# DE-300617.net
KiCad netlist of a schematic drawn in Altium Designer
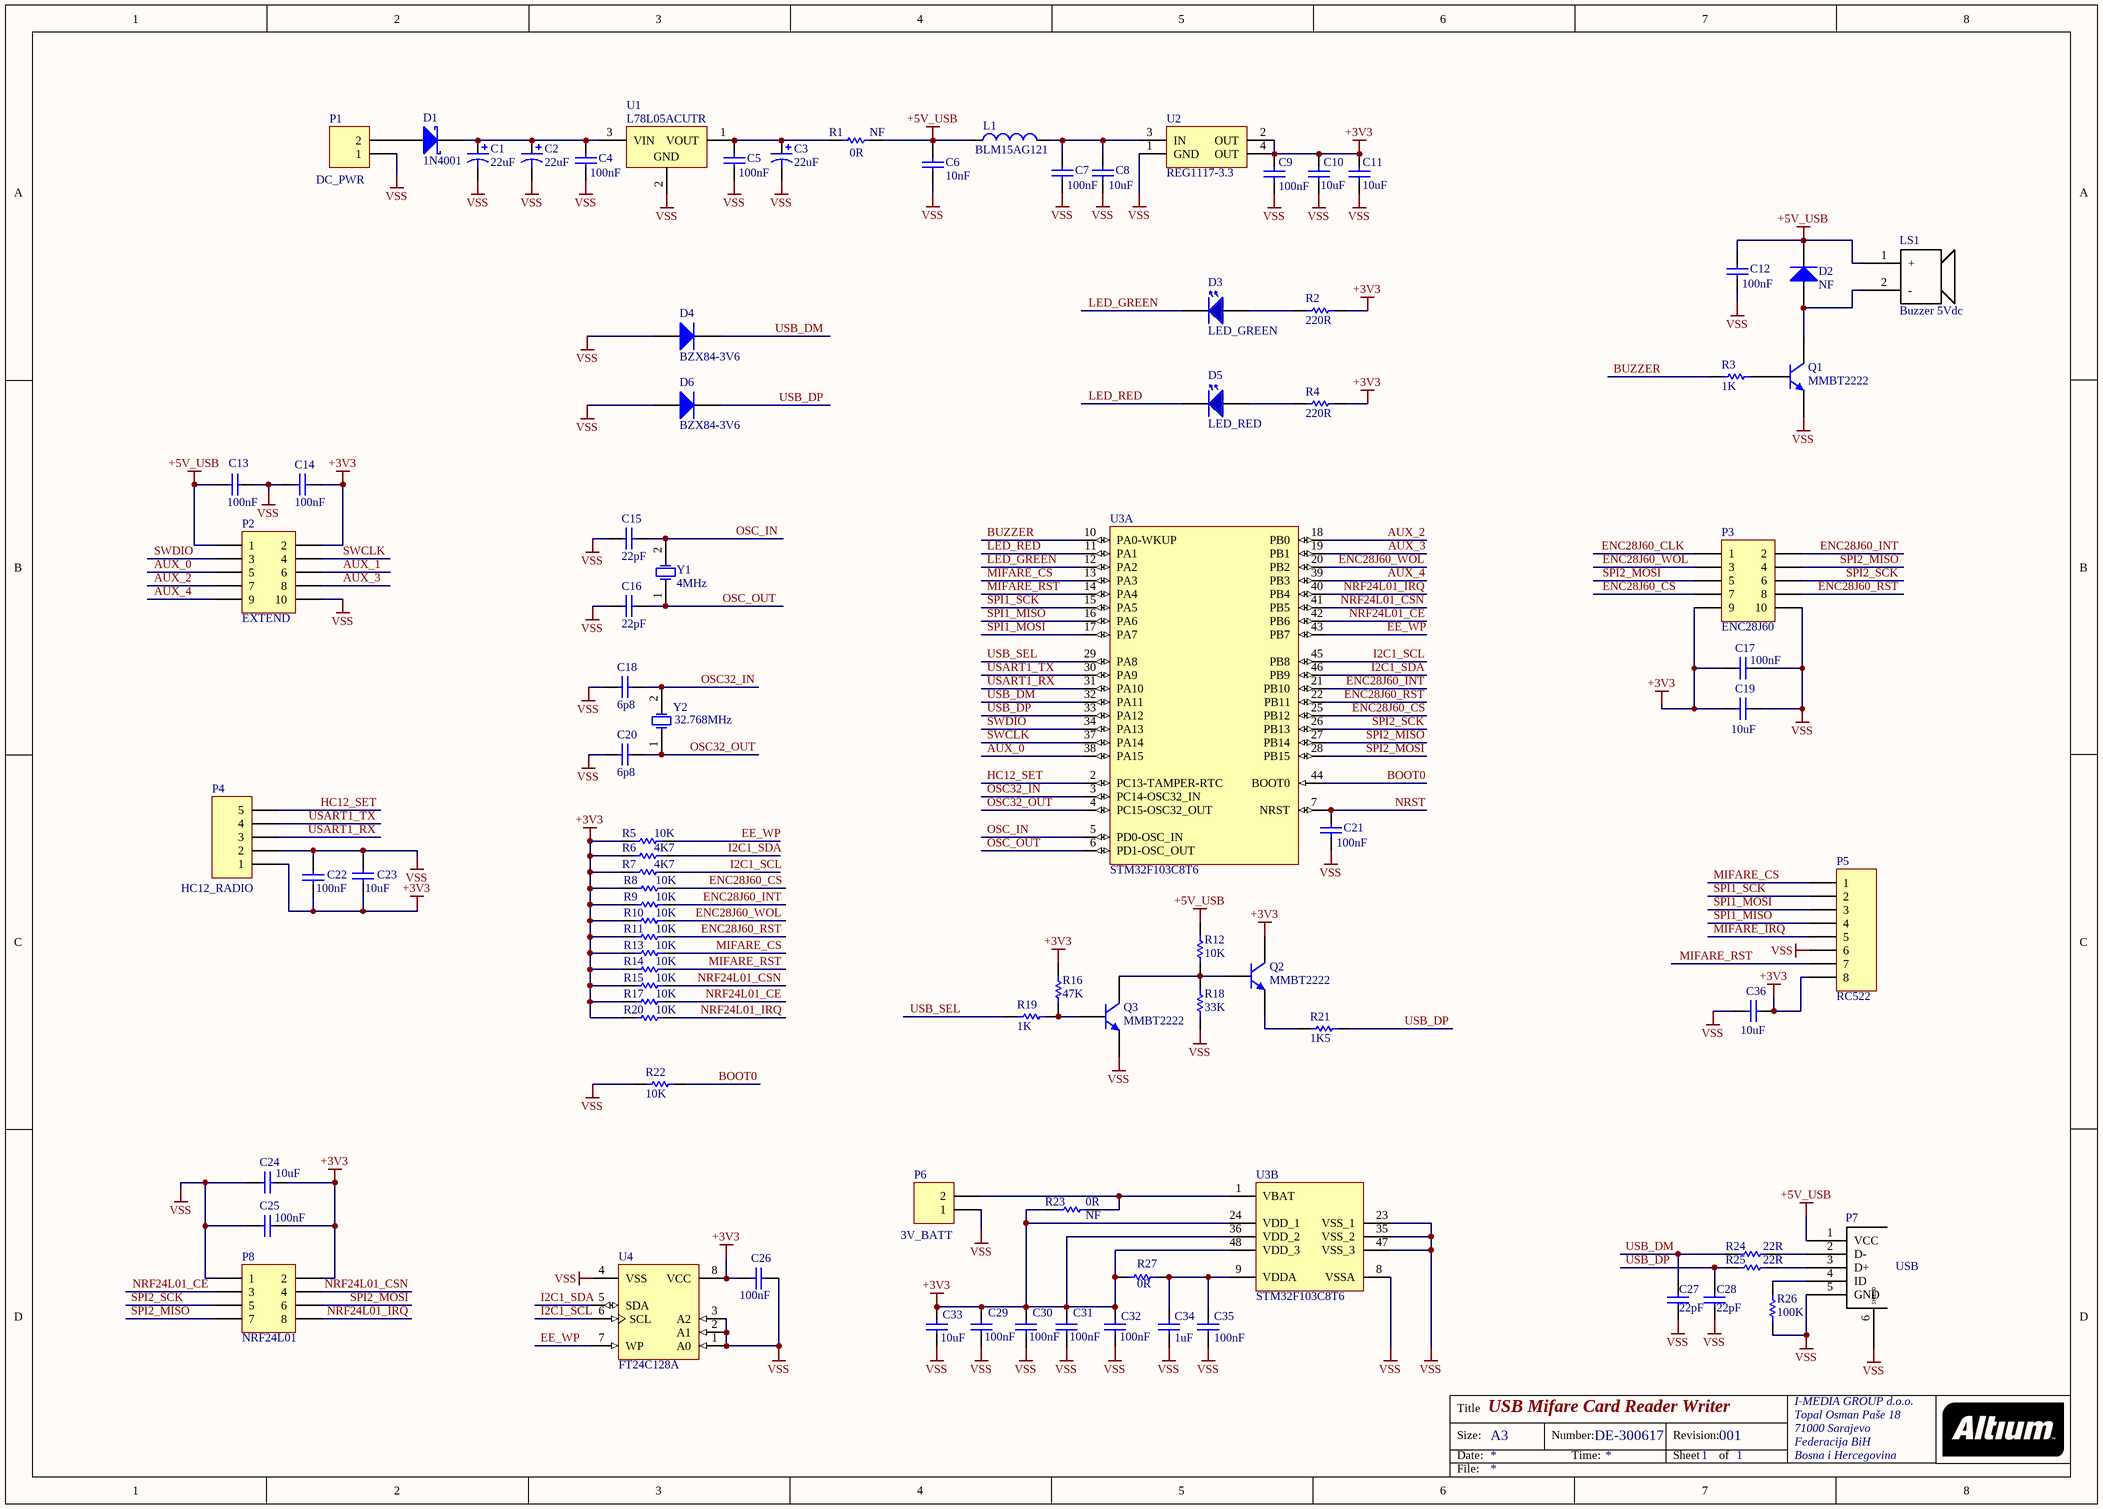
[diagram p0: DE-300617.SchDoc]

(export (version "E")
  (design (tool "Eeschema 10.0.6"))
  (components
    (comp (ref "C1")
      (value "22uF")
      (footprint "F")
      (fields (field (name "PUBLISHER") "Altium Limited"))
      (libsource (lib "Vishay Sprague Tantalum Chip Capacitor") (part "194D226X0015F2"))
    )
    (comp (ref "C2")
      (value "22uF")
      (footprint "F")
      (fields (field (name "PUBLISHER") "Altium Limited"))
      (libsource (lib "Vishay Sprague Tantalum Chip Capacitor") (part "194D226X0015F2"))
    )
    (comp (ref "C3")
      (value "22uF")
      (footprint "F")
      (fields (field (name "PUBLISHER") "Altium Limited"))
      (libsource (lib "Vishay Sprague Tantalum Chip Capacitor") (part "194D226X0015F2"))
    )
    (comp (ref "C4")
      (value "100nF")
      (footprint "0603")
      (description "Ceramic Chip Capacitor - Standard")
      (fields (field (name "PUBLISHER") "Altium Limited"))
      (libsource (lib "DE-300617") (part "C0603"))
    )
    (comp (ref "C5")
      (value "100nF")
      (footprint "0603")
      (description "Ceramic Chip Capacitor - Standard")
      (fields (field (name "PUBLISHER") "Altium Limited"))
      (libsource (lib "DE-300617") (part "C0603"))
    )
    (comp (ref "C6")
      (value "10nF")
      (footprint "0603")
      (description "Ceramic Chip Capacitor - Standard")
      (fields (field (name "PUBLISHER") "Altium Limited"))
      (libsource (lib "DE-300617") (part "C0603"))
    )
    (comp (ref "C7")
      (value "100nF")
      (footprint "0603")
      (description "Ceramic Chip Capacitor - Standard")
      (fields (field (name "PUBLISHER") "Altium Limited"))
      (libsource (lib "DE-300617") (part "C0603"))
    )
    (comp (ref "C8")
      (value "10uF")
      (footprint "0805")
      (description "Ceramic Chip Capacitor - Standard")
      (fields (field (name "PUBLISHER") "Altium Limited"))
      (libsource (lib "KEMET Chip Capacitor") (part "C0805"))
    )
    (comp (ref "C9")
      (value "100nF")
      (footprint "0603")
      (description "Ceramic Chip Capacitor - Standard")
      (fields (field (name "PUBLISHER") "Altium Limited"))
      (libsource (lib "DE-300617") (part "C0603"))
    )
    (comp (ref "C10")
      (value "10uF")
      (footprint "0805")
      (description "Ceramic Chip Capacitor - Standard")
      (fields (field (name "PUBLISHER") "Altium Limited"))
      (libsource (lib "KEMET Chip Capacitor") (part "C0805"))
    )
    (comp (ref "C11")
      (value "10uF")
      (footprint "0805")
      (description "Ceramic Chip Capacitor - Standard")
      (fields (field (name "PUBLISHER") "Altium Limited"))
      (libsource (lib "KEMET Chip Capacitor") (part "C0805"))
    )
    (comp (ref "C12")
      (value "100nF")
      (footprint "0603")
      (description "Ceramic Chip Capacitor - Standard")
      (fields (field (name "PUBLISHER") "Altium Limited"))
      (libsource (lib "DE-300617") (part "C0603"))
    )
    (comp (ref "C13")
      (value "100nF")
      (footprint "0603")
      (description "Ceramic Chip Capacitor - Standard")
      (fields (field (name "PUBLISHER") "Altium Limited"))
      (libsource (lib "DE-300617") (part "C0603"))
    )
    (comp (ref "C14")
      (value "100nF")
      (footprint "0603")
      (description "Ceramic Chip Capacitor - Standard")
      (fields (field (name "PUBLISHER") "Altium Limited"))
      (libsource (lib "DE-300617") (part "C0603"))
    )
    (comp (ref "C15")
      (value "22pF")
      (footprint "0603")
      (description "Ceramic Chip Capacitor - Standard")
      (fields (field (name "PUBLISHER") "Altium Limited"))
      (libsource (lib "DE-010116") (part "C0603"))
    )
    (comp (ref "C16")
      (value "22pF")
      (footprint "0603")
      (description "Ceramic Chip Capacitor - Standard")
      (fields (field (name "PUBLISHER") "Altium Limited"))
      (libsource (lib "DE-010116") (part "C0603"))
    )
    (comp (ref "C17")
      (value "100nF")
      (footprint "0805")
      (description "Ceramic Chip Capacitor - Standard")
      (fields (field (name "PUBLISHER") "Altium Limited"))
      (libsource (lib "KEMET Chip Capacitor") (part "C0805"))
    )
    (comp (ref "C18")
      (value "6p8")
      (footprint "0603")
      (description "Ceramic Chip Capacitor - Standard")
      (fields (field (name "PUBLISHER") "Altium Limited"))
      (libsource (lib "DE-010116") (part "C0603"))
    )
    (comp (ref "C19")
      (value "10uF")
      (footprint "0805")
      (description "Ceramic Chip Capacitor - Standard")
      (fields (field (name "PUBLISHER") "Altium Limited"))
      (libsource (lib "KEMET Chip Capacitor") (part "C0805"))
    )
    (comp (ref "C20")
      (value "6p8")
      (footprint "0603")
      (description "Ceramic Chip Capacitor - Standard")
      (fields (field (name "PUBLISHER") "Altium Limited"))
      (libsource (lib "DE-010116") (part "C0603"))
    )
    (comp (ref "C21")
      (value "100nF")
      (footprint "0603")
      (description "Ceramic Chip Capacitor - Standard")
      (fields (field (name "PUBLISHER") "Altium Limited"))
      (libsource (lib "DE-010116") (part "C0603"))
    )
    (comp (ref "C22")
      (value "100nF")
      (footprint "0805")
      (description "Ceramic Chip Capacitor - Standard")
      (fields (field (name "PUBLISHER") "Altium Limited"))
      (libsource (lib "KEMET Chip Capacitor") (part "C0805"))
    )
    (comp (ref "C23")
      (value "10uF")
      (footprint "0805")
      (description "Ceramic Chip Capacitor - Standard")
      (fields (field (name "PUBLISHER") "Altium Limited"))
      (libsource (lib "KEMET Chip Capacitor") (part "C0805"))
    )
    (comp (ref "C24")
      (value "10uF")
      (footprint "0805")
      (description "Ceramic Chip Capacitor - Standard")
      (fields (field (name "PUBLISHER") "Altium Limited"))
      (libsource (lib "KEMET Chip Capacitor") (part "C0805"))
    )
    (comp (ref "C25")
      (value "100nF")
      (footprint "0805")
      (description "Ceramic Chip Capacitor - Standard")
      (fields (field (name "PUBLISHER") "Altium Limited"))
      (libsource (lib "KEMET Chip Capacitor") (part "C0805"))
    )
    (comp (ref "C26")
      (value "100nF")
      (footprint "0603")
      (description "Ceramic Chip Capacitor - Standard")
      (fields (field (name "PUBLISHER") "Altium Limited"))
      (libsource (lib "DE-251215") (part "C0603"))
    )
    (comp (ref "C27")
      (value "22pF")
      (footprint "0603")
      (description "Ceramic Chip Capacitor - Standard")
      (fields (field (name "PUBLISHER") "Altium Limited"))
      (libsource (lib "KEMET Chip Capacitor") (part "C0603"))
    )
    (comp (ref "C28")
      (value "22pF")
      (footprint "0603")
      (description "Ceramic Chip Capacitor - Standard")
      (fields (field (name "PUBLISHER") "Altium Limited"))
      (libsource (lib "KEMET Chip Capacitor") (part "C0603"))
    )
    (comp (ref "C29")
      (value "100nF")
      (footprint "0603")
      (description "Ceramic Chip Capacitor - Standard")
      (fields (field (name "PUBLISHER") "Altium Limited"))
      (libsource (lib "DE-251215") (part "C0603"))
    )
    (comp (ref "C30")
      (value "100nF")
      (footprint "0603")
      (description "Ceramic Chip Capacitor - Standard")
      (fields (field (name "PUBLISHER") "Altium Limited"))
      (libsource (lib "DE-251215") (part "C0603"))
    )
    (comp (ref "C31")
      (value "100nF")
      (footprint "0603")
      (description "Ceramic Chip Capacitor - Standard")
      (fields (field (name "PUBLISHER") "Altium Limited"))
      (libsource (lib "DE-251215") (part "C0603"))
    )
    (comp (ref "C32")
      (value "100nF")
      (footprint "0603")
      (description "Ceramic Chip Capacitor - Standard")
      (fields (field (name "PUBLISHER") "Altium Limited"))
      (libsource (lib "DE-251215") (part "C0603"))
    )
    (comp (ref "C33")
      (value "10uF")
      (footprint "0805")
      (description "Ceramic Chip Capacitor - Standard")
      (fields (field (name "Comment") "4u7") (field (name "PUBLISHER") "Altium Limited"))
      (libsource (lib "DE-251215") (part "C0805"))
    )
    (comp (ref "C34")
      (value "1uF")
      (footprint "0603")
      (description "Ceramic Chip Capacitor - Standard")
      (fields (field (name "PUBLISHER") "Altium Limited"))
      (libsource (lib "DE-200216_01") (part "C0603"))
    )
    (comp (ref "C35")
      (value "100nF")
      (footprint "0603")
      (description "Ceramic Chip Capacitor - Standard")
      (fields (field (name "PUBLISHER") "Altium Limited"))
      (libsource (lib "DE-200216_01") (part "C0603"))
    )
    (comp (ref "C36")
      (value "10uF")
      (footprint "0805")
      (description "Ceramic Chip Capacitor - Standard")
      (fields (field (name "Comment") "C0805") (field (name "PUBLISHER") "Altium Limited"))
      (libsource (lib "KEMET Chip Capacitor") (part "C0805"))
    )
    (comp (ref "D1")
      (value "1N4001")
      (footprint "SMA")
      (description "Schottky Rectifier")
      (fields (field (name "PUBLISHER") "Altium Limited"))
      (libsource (lib "IR Rectifier - Schottky") (part "10MQ060N"))
    )
    (comp (ref "D2")
      (value "NF")
      (footprint "SOD323")
      (description "General-purpose Diode")
      (fields (field (name "PUBLISHER") "Altium Limited"))
      (libsource (lib "DE-300617") (part "BAS321"))
    )
    (comp (ref "D3") (value "LED_GREEN") (footprint "LED 3mm") (libsource (lib "DE-300617") (part "LED 3mm")))
    (comp (ref "D4")
      (value "BZX84-3V6")
      (footprint "SOT23_N")
      (description "Voltage Regulator Diode")
      (fields (field (name "PUBLISHER") "Altium Limited"))
      (libsource (lib "DE-300617") (part "BZX84-A4V7"))
    )
    (comp (ref "D5") (value "LED_RED") (footprint "LED 3mm") (libsource (lib "DE-300617") (part "LED 3mm")))
    (comp (ref "D6")
      (value "BZX84-3V6")
      (footprint "SOT23_N")
      (description "Voltage Regulator Diode")
      (fields (field (name "PUBLISHER") "Altium Limited"))
      (libsource (lib "DE-300617") (part "BZX84-A4V7"))
    )
    (comp (ref "L1")
      (value "BLM15AG121")
      (footprint "0402-A")
      (description "SMD chip inductor")
      (fields (field (name "PUBLISHER") "Altium Limited"))
      (libsource (lib "DE-300617") (part "Chip inductor"))
    )
    (comp (ref "LS1")
      (value "Buzzer 5Vdc")
      (footprint "BUZZER")
      (description "5Vdc PCB buzzer")
      (libsource (lib "DE-300617") (part "BUZZER"))
    )
    (comp (ref "P1")
      (value "DC_PWR")
      (footprint "HDR1X2")
      (description "Header, 2-Pin")
      (fields (field (name "PUBLISHER") "Altium Limited"))
      (libsource (lib "Miscellaneous Connectors") (part "Header 2"))
    )
    (comp (ref "P2")
      (value "EXTEND")
      (footprint "HDR2X5")
      (description "Header, 5-Pin, Dual row")
      (fields (field (name "PUBLISHER") "Altium Limited"))
      (libsource (lib "Miscellaneous Connectors") (part "Header 5X2"))
    )
    (comp (ref "P3")
      (value "ENC28J60")
      (footprint "HDR2X5")
      (description "Header, 5-Pin, Dual row")
      (fields (field (name "PUBLISHER") "Altium Limited"))
      (libsource (lib "Miscellaneous Connectors") (part "Header 5X2"))
    )
    (comp (ref "P4")
      (value "HC12_RADIO")
      (footprint "HDR1X5")
      (description "Header, 5-Pin")
      (fields (field (name "PUBLISHER") "Altium Limited"))
      (libsource (lib "Miscellaneous Connectors") (part "Header 5"))
    )
    (comp (ref "P5")
      (value "RC522")
      (footprint "HDR1X8")
      (description "Header, 8-Pin")
      (fields (field (name "PUBLISHER") "Altium Limited"))
      (libsource (lib "Miscellaneous Connectors") (part "Header 8"))
    )
    (comp (ref "P6")
      (value "3V_BATT")
      (footprint "HDR1X2")
      (description "Header, 2-Pin")
      (fields (field (name "PUBLISHER") "Altium Limited"))
      (libsource (lib "Miscellaneous Connectors") (part "Header 2"))
    )
    (comp (ref "P7")
      (value "USB")
      (footprint "USB mini B")
      (description "USB connector B mini")
      (libsource (lib "DE-300617") (part "USB mini B"))
    )
    (comp (ref "P8")
      (value "NRF24L01")
      (footprint "HDR2X4")
      (description "Header, 4-Pin, Dual row")
      (fields (field (name "PUBLISHER") "Altium Limited"))
      (libsource (lib "Miscellaneous Connectors") (part "Header 4X2"))
    )
    (comp (ref "Q1")
      (value "MMBT2222")
      (footprint "SOT23_N")
      (description "NPN General-purpose Transistor")
      (fields (field (name "PUBLISHER") "Altium Limited"))
      (libsource (lib "DE-300617") (part "BC817"))
    )
    (comp (ref "Q2")
      (value "MMBT2222")
      (footprint "SOT23_N")
      (description "NPN General-purpose Transistor")
      (fields (field (name "PUBLISHER") "Altium Limited"))
      (libsource (lib "DE-300617") (part "BC817"))
    )
    (comp (ref "Q3")
      (value "MMBT2222")
      (footprint "SOT23_N")
      (description "NPN General-purpose Transistor")
      (fields (field (name "PUBLISHER") "Altium Limited"))
      (libsource (lib "DE-300617") (part "BC817"))
    )
    (comp (ref "R1")
      (value "0R")
      (footprint "ERA-0603")
      (fields (field (name "ALTIUM_VALUE") "NF") (field (name "PUBLISHER") "Altium Limited"))
      (libsource (lib "DE-010116") (part "ERAV"))
    )
    (comp (ref "R2")
      (value "220R")
      (footprint "ERA-0603")
      (fields (field (name "PUBLISHER") "Altium Limited"))
      (libsource (lib "DE-010116") (part "ERAV"))
    )
    (comp (ref "R3")
      (value "1K")
      (footprint "ERA-0603")
      (fields (field (name "PUBLISHER") "Altium Limited"))
      (libsource (lib "DE-010116") (part "ERAV"))
    )
    (comp (ref "R4")
      (value "220R")
      (footprint "ERA-0603")
      (fields (field (name "PUBLISHER") "Altium Limited"))
      (libsource (lib "DE-010116") (part "ERAV"))
    )
    (comp (ref "R5")
      (value "10K")
      (footprint "ERA-0603")
      (fields (field (name "PUBLISHER") "Altium Limited"))
      (libsource (lib "DE-251215") (part "ERAV"))
    )
    (comp (ref "R6")
      (value "4K7")
      (footprint "ERA-0603")
      (fields (field (name "PUBLISHER") "Altium Limited"))
      (libsource (lib "DE-251215") (part "ERAV"))
    )
    (comp (ref "R7")
      (value "4K7")
      (footprint "ERA-0603")
      (fields (field (name "PUBLISHER") "Altium Limited"))
      (libsource (lib "DE-251215") (part "ERAV"))
    )
    (comp (ref "R8")
      (value "10K")
      (footprint "ERA-0603")
      (fields (field (name "PUBLISHER") "Altium Limited"))
      (libsource (lib "DE-251215") (part "ERAV"))
    )
    (comp (ref "R9")
      (value "10K")
      (footprint "ERA-0603")
      (fields (field (name "PUBLISHER") "Altium Limited"))
      (libsource (lib "DE-251215") (part "ERAV"))
    )
    (comp (ref "R10")
      (value "10K")
      (footprint "ERA-0603")
      (fields (field (name "PUBLISHER") "Altium Limited"))
      (libsource (lib "DE-251215") (part "ERAV"))
    )
    (comp (ref "R11")
      (value "10K")
      (footprint "ERA-0603")
      (fields (field (name "PUBLISHER") "Altium Limited"))
      (libsource (lib "DE-251215") (part "ERAV"))
    )
    (comp (ref "R12")
      (value "10K")
      (footprint "ERA-0603")
      (fields (field (name "PUBLISHER") "Altium Limited"))
      (libsource (lib "DE-010116") (part "ERAV"))
    )
    (comp (ref "R13")
      (value "10K")
      (footprint "ERA-0603")
      (fields (field (name "PUBLISHER") "Altium Limited"))
      (libsource (lib "DE-251215") (part "ERAV"))
    )
    (comp (ref "R14")
      (value "10K")
      (footprint "ERA-0603")
      (fields (field (name "PUBLISHER") "Altium Limited"))
      (libsource (lib "DE-251215") (part "ERAV"))
    )
    (comp (ref "R15")
      (value "10K")
      (footprint "ERA-0603")
      (fields (field (name "PUBLISHER") "Altium Limited"))
      (libsource (lib "DE-251215") (part "ERAV"))
    )
    (comp (ref "R16")
      (value "47K")
      (footprint "ERA-0603")
      (fields (field (name "PUBLISHER") "Altium Limited"))
      (libsource (lib "DE-010116") (part "ERAV"))
    )
    (comp (ref "R17")
      (value "10K")
      (footprint "ERA-0603")
      (fields (field (name "PUBLISHER") "Altium Limited"))
      (libsource (lib "DE-251215") (part "ERAV"))
    )
    (comp (ref "R18")
      (value "33K")
      (footprint "ERA-0603")
      (fields (field (name "PUBLISHER") "Altium Limited"))
      (libsource (lib "DE-010116") (part "ERAV"))
    )
    (comp (ref "R19")
      (value "1K")
      (footprint "ERA-0603")
      (fields (field (name "PUBLISHER") "Altium Limited"))
      (libsource (lib "DE-010116") (part "ERAV"))
    )
    (comp (ref "R20")
      (value "10K")
      (footprint "ERA-0603")
      (fields (field (name "PUBLISHER") "Altium Limited"))
      (libsource (lib "DE-251215") (part "ERAV"))
    )
    (comp (ref "R21")
      (value "1K5")
      (footprint "ERA-0603")
      (fields (field (name "PUBLISHER") "Altium Limited"))
      (libsource (lib "DE-010116") (part "ERAV"))
    )
    (comp (ref "R22")
      (value "10K")
      (footprint "ERA-0603")
      (fields (field (name "PUBLISHER") "Altium Limited"))
      (libsource (lib "DE-010116") (part "ERAV"))
    )
    (comp (ref "R23")
      (value "0R")
      (footprint "ERA-0603")
      (fields (field (name "ALTIUM_VALUE") "NF") (field (name "PUBLISHER") "Altium Limited"))
      (libsource (lib "DE-010116") (part "ERAV"))
    )
    (comp (ref "R24")
      (value "22R")
      (footprint "ERA-0603")
      (fields (field (name "PUBLISHER") "Altium Limited"))
      (libsource (lib "Panasonic Resistor") (part "ERA3Y"))
    )
    (comp (ref "R25")
      (value "22R")
      (footprint "ERA-0603")
      (fields (field (name "PUBLISHER") "Altium Limited"))
      (libsource (lib "Panasonic Resistor") (part "ERA3Y"))
    )
    (comp (ref "R26")
      (value "100K")
      (footprint "ERA-0603")
      (fields (field (name "PUBLISHER") "Altium Limited"))
      (libsource (lib "Panasonic Resistor") (part "ERA3Y"))
    )
    (comp (ref "R27")
      (value "0R")
      (footprint "ERA-0603")
      (fields (field (name "PUBLISHER") "Altium Limited"))
      (libsource (lib "DE-010116") (part "ERAV"))
    )
    (comp (ref "U1")
      (value "L78L05ACUTR")
      (footprint "SOT-89_N")
      (description "Positive Voltage Regulator, 5V, 4-Pin SOT-89, Tape and Reel")
      (libsource (lib "DE-300617") (part "L78L05ACUTR"))
    )
    (comp (ref "U2")
      (value "REG1117-3.3")
      (footprint "ZZ311")
      (description "800mA and 1A Low Dropout Positive Regulator 2.85V, 3.3V, 5V, and Adjustable")
      (fields (field (name "PUBLISHER") "Altium Limited"))
      (libsource (lib "DE-300617") (part "REG1117-3.3"))
    )
    (comp (ref "U3")
      (value "STM32F103C8T6")
      (footprint "STM-LQFP48_N")
      (libsource (lib "STMicroelectronics STM32 F1") (part "STM32F103C8T6"))
    )
    (comp (ref "U4")
      (value "FT24C128A")
      (footprint "SOIC-SN8_N")
      (description "64Kbit, 400kHz, 1.7V, I2C Serial EEPROM, 8-Pin SOIC 150mil, Commercial Temperature")
      (fields (field (name "PUBLISHER") "Altium Limited"))
      (libsource (lib "Microchip Memory I2C Serial EEPROM") (part "24AA64/SN"))
    )
    (comp (ref "Y1")
      (value "4MHz")
      (footprint "HC49/4H_SMX")
      (description "Surface Mount Quartz Crystal")
      (fields (field (name "PUBLISHER") "Altium Limited"))
      (libsource (lib "DE-200216_02") (part "HC49/4H_SMX"))
    )
    (comp (ref "Y2")
      (value "32.768MHz")
      (footprint "R26")
      (description "Tuning Fork Crystal Unit")
      (fields (field (name "PUBLISHER") "Altium Limited"))
      (libsource (lib "Raltron Crystal Oscillator") (part "R26-32.768"))
    )
  )
  (nets
    (net (code "1") (name "+3V3") (class "Default")
      (node (ref "C10") (pin "1") (pinfunction "1_1") (pintype "passive"))
      (node (ref "C11") (pin "1") (pinfunction "1_1") (pintype "passive"))
      (node (ref "C14") (pin "2") (pinfunction "2_2") (pintype "passive"))
      (node (ref "C17") (pin "1") (pinfunction "1_1") (pintype "passive"))
      (node (ref "C19") (pin "2") (pinfunction "2_2") (pintype "passive"))
      (node (ref "C22") (pin "1") (pinfunction "1_1") (pintype "passive"))
      (node (ref "C23") (pin "2") (pinfunction "2_2") (pintype "passive"))
      (node (ref "C24") (pin "1") (pinfunction "1_1") (pintype "passive"))
      (node (ref "C25") (pin "2") (pinfunction "2_2") (pintype "passive"))
      (node (ref "C26") (pin "1") (pinfunction "1_1") (pintype "passive"))
      (node (ref "C29") (pin "2") (pinfunction "2_2") (pintype "passive"))
      (node (ref "C30") (pin "2") (pinfunction "2_2") (pintype "passive"))
      (node (ref "C31") (pin "2") (pinfunction "2_2") (pintype "passive"))
      (node (ref "C32") (pin "2") (pinfunction "2_2") (pintype "passive"))
      (node (ref "C33") (pin "2") (pinfunction "2_2") (pintype "passive"))
      (node (ref "C36") (pin "2") (pinfunction "2_2") (pintype "passive"))
      (node (ref "C9") (pin "2") (pinfunction "2_2") (pintype "passive"))
      (node (ref "P2") (pin "2") (pinfunction "2_2") (pintype "passive"))
      (node (ref "P3") (pin "9") (pinfunction "9_9") (pintype "passive"))
      (node (ref "P4") (pin "1") (pinfunction "1_1") (pintype "passive"))
      (node (ref "P5") (pin "8") (pinfunction "8_8") (pintype "passive"))
      (node (ref "P8") (pin "2") (pinfunction "2_2") (pintype "passive"))
      (node (ref "Q2") (pin "3") (pinfunction "C_3") (pintype "passive"))
      (node (ref "R10") (pin "2") (pinfunction "2_2") (pintype "passive"))
      (node (ref "R11") (pin "2") (pinfunction "2_2") (pintype "passive"))
      (node (ref "R13") (pin "2") (pinfunction "2_2") (pintype "passive"))
      (node (ref "R14") (pin "2") (pinfunction "2_2") (pintype "passive"))
      (node (ref "R15") (pin "2") (pinfunction "2_2") (pintype "passive"))
      (node (ref "R16") (pin "1") (pinfunction "1_1") (pintype "passive"))
      (node (ref "R17") (pin "2") (pinfunction "2_2") (pintype "passive"))
      (node (ref "R2") (pin "1") (pinfunction "1_1") (pintype "passive"))
      (node (ref "R20") (pin "2") (pinfunction "2_2") (pintype "passive"))
      (node (ref "R23") (pin "2") (pinfunction "2_2") (pintype "passive"))
      (node (ref "R27") (pin "2") (pinfunction "2_2") (pintype "passive"))
      (node (ref "R4") (pin "1") (pinfunction "1_1") (pintype "passive"))
      (node (ref "R5") (pin "2") (pinfunction "2_2") (pintype "passive"))
      (node (ref "R6") (pin "2") (pinfunction "2_2") (pintype "passive"))
      (node (ref "R7") (pin "2") (pinfunction "2_2") (pintype "passive"))
      (node (ref "R8") (pin "2") (pinfunction "2_2") (pintype "passive"))
      (node (ref "R9") (pin "2") (pinfunction "2_2") (pintype "passive"))
      (node (ref "U2") (pin "2") (pinfunction "OUT_2") (pintype "power_in"))
      (node (ref "U2") (pin "4") (pinfunction "OUT_4") (pintype "power_in"))
      (node (ref "U3") (pin "24") (pinfunction "VDD_1_24") (pintype "power_in"))
      (node (ref "U3") (pin "36") (pinfunction "VDD_2_36") (pintype "power_in"))
      (node (ref "U3") (pin "48") (pinfunction "VDD_3_48") (pintype "power_in"))
      (node (ref "U4") (pin "8") (pinfunction "VCC_8") (pintype "power_in"))
    )
    (net (code "2") (name "+5V_USB") (class "Default")
      (node (ref "C12") (pin "2") (pinfunction "2_2") (pintype "passive"))
      (node (ref "C13") (pin "1") (pinfunction "1_1") (pintype "passive"))
      (node (ref "C6") (pin "2") (pinfunction "2_2") (pintype "passive"))
      (node (ref "D2") (pin "1") (pinfunction "K_1") (pintype "passive"))
      (node (ref "L1") (pin "1") (pinfunction "1_1") (pintype "passive"))
      (node (ref "LS1") (pin "1") (pinfunction "+_1") (pintype "passive"))
      (node (ref "P2") (pin "1") (pinfunction "1_1") (pintype "passive"))
      (node (ref "P7") (pin "1") (pinfunction "VCC_1") (pintype "passive"))
      (node (ref "R1") (pin "1") (pinfunction "1_1") (pintype "passive"))
      (node (ref "R12") (pin "1") (pinfunction "1_1") (pintype "passive"))
    )
    (net (code "3") (name "/AUX_0") (class "Default")
      (node (ref "P2") (pin "5") (pinfunction "5_5") (pintype "passive"))
      (node (ref "U3") (pin "38") (pinfunction "PA15_38") (pintype "bidirectional"))
    )
    (net (code "4") (name "/AUX_1") (class "Default")
      (node (ref "P2") (pin "6") (pinfunction "6_6") (pintype "passive"))
    )
    (net (code "5") (name "/AUX_2") (class "Default")
      (node (ref "P2") (pin "7") (pinfunction "7_7") (pintype "passive"))
      (node (ref "U3") (pin "18") (pinfunction "PB0_18") (pintype "bidirectional"))
    )
    (net (code "6") (name "/AUX_3") (class "Default")
      (node (ref "P2") (pin "8") (pinfunction "8_8") (pintype "passive"))
      (node (ref "U3") (pin "19") (pinfunction "PB1_19") (pintype "bidirectional"))
    )
    (net (code "7") (name "/AUX_4") (class "Default")
      (node (ref "P2") (pin "9") (pinfunction "9_9") (pintype "passive"))
      (node (ref "U3") (pin "39") (pinfunction "PB3_39") (pintype "bidirectional"))
    )
    (net (code "8") (name "/BOOT0") (class "Default")
      (node (ref "R22") (pin "1") (pinfunction "1_1") (pintype "passive"))
      (node (ref "U3") (pin "44") (pinfunction "BOOT0_44") (pintype "input"))
    )
    (net (code "9") (name "/BUZZER") (class "Default")
      (node (ref "R3") (pin "2") (pinfunction "2_2") (pintype "passive"))
      (node (ref "U3") (pin "10") (pinfunction "PA0-WKUP_10") (pintype "bidirectional"))
    )
    (net (code "10") (name "/EE_WP") (class "Default")
      (node (ref "R5") (pin "1") (pinfunction "1_1") (pintype "passive"))
      (node (ref "U3") (pin "43") (pinfunction "PB7_43") (pintype "bidirectional"))
      (node (ref "U4") (pin "7") (pinfunction "WP_7") (pintype "input"))
    )
    (net (code "11") (name "/ENC28J60_CLK") (class "Default")
      (node (ref "P3") (pin "1") (pinfunction "1_1") (pintype "passive"))
    )
    (net (code "12") (name "/ENC28J60_CS") (class "Default")
      (node (ref "P3") (pin "7") (pinfunction "7_7") (pintype "passive"))
      (node (ref "R8") (pin "1") (pinfunction "1_1") (pintype "passive"))
      (node (ref "U3") (pin "25") (pinfunction "PB12_25") (pintype "bidirectional"))
    )
    (net (code "13") (name "/ENC28J60_INT") (class "Default")
      (node (ref "P3") (pin "2") (pinfunction "2_2") (pintype "passive"))
      (node (ref "R9") (pin "1") (pinfunction "1_1") (pintype "passive"))
      (node (ref "U3") (pin "21") (pinfunction "PB10_21") (pintype "bidirectional"))
    )
    (net (code "14") (name "/ENC28J60_RST") (class "Default")
      (node (ref "P3") (pin "8") (pinfunction "8_8") (pintype "passive"))
      (node (ref "R11") (pin "1") (pinfunction "1_1") (pintype "passive"))
      (node (ref "U3") (pin "22") (pinfunction "PB11_22") (pintype "bidirectional"))
    )
    (net (code "15") (name "/ENC28J60_WOL") (class "Default")
      (node (ref "P3") (pin "3") (pinfunction "3_3") (pintype "passive"))
      (node (ref "R10") (pin "1") (pinfunction "1_1") (pintype "passive"))
      (node (ref "U3") (pin "20") (pinfunction "PB2_20") (pintype "bidirectional"))
    )
    (net (code "16") (name "/HC12_SET") (class "Default")
      (node (ref "P4") (pin "5") (pinfunction "5_5") (pintype "passive"))
      (node (ref "U3") (pin "2") (pinfunction "PC13-TAMPER-RTC_2") (pintype "bidirectional"))
    )
    (net (code "17") (name "/I2C1_SCL") (class "Default")
      (node (ref "R7") (pin "1") (pinfunction "1_1") (pintype "passive"))
      (node (ref "U3") (pin "45") (pinfunction "PB8_45") (pintype "bidirectional"))
      (node (ref "U4") (pin "6") (pinfunction "SCL_6") (pintype "input"))
    )
    (net (code "18") (name "/I2C1_SDA") (class "Default")
      (node (ref "R6") (pin "1") (pinfunction "1_1") (pintype "passive"))
      (node (ref "U3") (pin "46") (pinfunction "PB9_46") (pintype "bidirectional"))
      (node (ref "U4") (pin "5") (pinfunction "SDA_5") (pintype "bidirectional"))
    )
    (net (code "19") (name "/LED_GREEN") (class "Default")
      (node (ref "D3") (pin "1") (pinfunction "1_1") (pintype "passive"))
      (node (ref "U3") (pin "12") (pinfunction "PA2_12") (pintype "bidirectional"))
    )
    (net (code "20") (name "/LED_RED") (class "Default")
      (node (ref "D5") (pin "1") (pinfunction "1_1") (pintype "passive"))
      (node (ref "U3") (pin "11") (pinfunction "PA1_11") (pintype "bidirectional"))
    )
    (net (code "21") (name "/MIFARE_CS") (class "Default")
      (node (ref "P5") (pin "1") (pinfunction "1_1") (pintype "passive"))
      (node (ref "R13") (pin "1") (pinfunction "1_1") (pintype "passive"))
      (node (ref "U3") (pin "13") (pinfunction "PA3_13") (pintype "bidirectional"))
    )
    (net (code "22") (name "/MIFARE_IRQ") (class "Default")
      (node (ref "P5") (pin "5") (pinfunction "5_5") (pintype "passive"))
    )
    (net (code "23") (name "/MIFARE_RST") (class "Default")
      (node (ref "P5") (pin "7") (pinfunction "7_7") (pintype "passive"))
      (node (ref "R14") (pin "1") (pinfunction "1_1") (pintype "passive"))
      (node (ref "U3") (pin "14") (pinfunction "PA4_14") (pintype "bidirectional"))
    )
    (net (code "24") (name "/NRF24L01_CE") (class "Default")
      (node (ref "P8") (pin "3") (pinfunction "3_3") (pintype "passive"))
      (node (ref "R17") (pin "1") (pinfunction "1_1") (pintype "passive"))
      (node (ref "U3") (pin "42") (pinfunction "PB6_42") (pintype "bidirectional"))
    )
    (net (code "25") (name "/NRF24L01_CSN") (class "Default")
      (node (ref "P8") (pin "4") (pinfunction "4_4") (pintype "passive"))
      (node (ref "R15") (pin "1") (pinfunction "1_1") (pintype "passive"))
      (node (ref "U3") (pin "41") (pinfunction "PB5_41") (pintype "bidirectional"))
    )
    (net (code "26") (name "/NRF24L01_IRQ") (class "Default")
      (node (ref "P8") (pin "8") (pinfunction "8_8") (pintype "passive"))
      (node (ref "R20") (pin "1") (pinfunction "1_1") (pintype "passive"))
      (node (ref "U3") (pin "40") (pinfunction "PB4_40") (pintype "bidirectional"))
    )
    (net (code "27") (name "/NRST") (class "Default")
      (node (ref "C21") (pin "1") (pinfunction "1_1") (pintype "passive"))
      (node (ref "U3") (pin "7") (pinfunction "NRST_7") (pintype "bidirectional"))
    )
    (net (code "28") (name "/OSC32_IN") (class "Default")
      (node (ref "C18") (pin "1") (pinfunction "1_1") (pintype "passive"))
      (node (ref "U3") (pin "3") (pinfunction "PC14-OSC32_IN_3") (pintype "bidirectional"))
      (node (ref "Y2") (pin "2") (pinfunction "OSC2_2") (pintype "passive"))
    )
    (net (code "29") (name "/OSC32_OUT") (class "Default")
      (node (ref "C20") (pin "1") (pinfunction "1_1") (pintype "passive"))
      (node (ref "U3") (pin "4") (pinfunction "PC15-OSC32_OUT_4") (pintype "bidirectional"))
      (node (ref "Y2") (pin "1") (pinfunction "OSC1_1") (pintype "passive"))
    )
    (net (code "30") (name "/OSC_IN") (class "Default")
      (node (ref "C15") (pin "1") (pinfunction "1_1") (pintype "passive"))
      (node (ref "U3") (pin "5") (pinfunction "PD0-OSC_IN_5") (pintype "bidirectional"))
      (node (ref "Y1") (pin "2") (pinfunction "OSC2_2") (pintype "passive"))
    )
    (net (code "31") (name "/OSC_OUT") (class "Default")
      (node (ref "C16") (pin "1") (pinfunction "1_1") (pintype "passive"))
      (node (ref "U3") (pin "6") (pinfunction "PD1-OSC_OUT_6") (pintype "bidirectional"))
      (node (ref "Y1") (pin "1") (pinfunction "OSC1_1") (pintype "passive"))
    )
    (net (code "32") (name "/SPI1_MISO") (class "Default")
      (node (ref "P5") (pin "4") (pinfunction "4_4") (pintype "passive"))
      (node (ref "U3") (pin "16") (pinfunction "PA6_16") (pintype "bidirectional"))
    )
    (net (code "33") (name "/SPI1_MOSI") (class "Default")
      (node (ref "P5") (pin "3") (pinfunction "3_3") (pintype "passive"))
      (node (ref "U3") (pin "17") (pinfunction "PA7_17") (pintype "bidirectional"))
    )
    (net (code "34") (name "/SPI1_SCK") (class "Default")
      (node (ref "P5") (pin "2") (pinfunction "2_2") (pintype "passive"))
      (node (ref "U3") (pin "15") (pinfunction "PA5_15") (pintype "bidirectional"))
    )
    (net (code "35") (name "/SPI2_MISO") (class "Default")
      (node (ref "P3") (pin "4") (pinfunction "4_4") (pintype "passive"))
      (node (ref "P8") (pin "7") (pinfunction "7_7") (pintype "passive"))
      (node (ref "U3") (pin "27") (pinfunction "PB14_27") (pintype "bidirectional"))
    )
    (net (code "36") (name "/SPI2_MOSI") (class "Default")
      (node (ref "P3") (pin "5") (pinfunction "5_5") (pintype "passive"))
      (node (ref "P8") (pin "6") (pinfunction "6_6") (pintype "passive"))
      (node (ref "U3") (pin "28") (pinfunction "PB15_28") (pintype "bidirectional"))
    )
    (net (code "37") (name "/SPI2_SCK") (class "Default")
      (node (ref "P3") (pin "6") (pinfunction "6_6") (pintype "passive"))
      (node (ref "P8") (pin "5") (pinfunction "5_5") (pintype "passive"))
      (node (ref "U3") (pin "26") (pinfunction "PB13_26") (pintype "bidirectional"))
    )
    (net (code "38") (name "/SWCLK") (class "Default")
      (node (ref "P2") (pin "4") (pinfunction "4_4") (pintype "passive"))
      (node (ref "U3") (pin "37") (pinfunction "PA14_37") (pintype "bidirectional"))
    )
    (net (code "39") (name "/SWDIO") (class "Default")
      (node (ref "P2") (pin "3") (pinfunction "3_3") (pintype "passive"))
      (node (ref "U3") (pin "34") (pinfunction "PA13_34") (pintype "bidirectional"))
    )
    (net (code "40") (name "/USART1_RX") (class "Default")
      (node (ref "P4") (pin "3") (pinfunction "3_3") (pintype "passive"))
      (node (ref "U3") (pin "31") (pinfunction "PA10_31") (pintype "bidirectional"))
    )
    (net (code "41") (name "/USART1_TX") (class "Default")
      (node (ref "P4") (pin "4") (pinfunction "4_4") (pintype "passive"))
      (node (ref "U3") (pin "30") (pinfunction "PA9_30") (pintype "bidirectional"))
    )
    (net (code "42") (name "/USB_DM") (class "Default")
      (node (ref "C27") (pin "2") (pinfunction "2_2") (pintype "passive"))
      (node (ref "D4") (pin "3") (pinfunction "K_3") (pintype "passive"))
      (node (ref "R24") (pin "1") (pinfunction "1_1") (pintype "passive"))
      (node (ref "U3") (pin "32") (pinfunction "PA11_32") (pintype "bidirectional"))
    )
    (net (code "43") (name "/USB_DP") (class "Default")
      (node (ref "C28") (pin "2") (pinfunction "2_2") (pintype "passive"))
      (node (ref "D6") (pin "3") (pinfunction "K_3") (pintype "passive"))
      (node (ref "R21") (pin "1") (pinfunction "1_1") (pintype "passive"))
      (node (ref "R25") (pin "1") (pinfunction "1_1") (pintype "passive"))
      (node (ref "U3") (pin "33") (pinfunction "PA12_33") (pintype "bidirectional"))
    )
    (net (code "44") (name "/USB_SEL") (class "Default")
      (node (ref "R19") (pin "1") (pinfunction "1_1") (pintype "passive"))
      (node (ref "U3") (pin "29") (pinfunction "PA8_29") (pintype "bidirectional"))
    )
    (net (code "45") (name "Net-(D1-A)") (class "Default")
      (node (ref "D1") (pin "1") (pinfunction "A_1") (pintype "passive"))
      (node (ref "P1") (pin "2") (pinfunction "2_2") (pintype "passive"))
    )
    (net (code "46") (name "Net-(D1-K)") (class "Default")
      (node (ref "C1") (pin "1") (pinfunction "1_1") (pintype "passive"))
      (node (ref "C2") (pin "1") (pinfunction "1_1") (pintype "passive"))
      (node (ref "C4") (pin "2") (pinfunction "2_2") (pintype "passive"))
      (node (ref "D1") (pin "2") (pinfunction "K_2") (pintype "passive"))
      (node (ref "U1") (pin "3") (pinfunction "VIN_3") (pintype "power_in"))
    )
    (net (code "47") (name "Net-(D2-A)") (class "Default")
      (node (ref "D2") (pin "2") (pinfunction "A_2") (pintype "passive"))
      (node (ref "LS1") (pin "2") (pinfunction "-_2") (pintype "passive"))
      (node (ref "Q1") (pin "3") (pinfunction "C_3") (pintype "passive"))
    )
    (net (code "48") (name "Net-(D3-Pad2)") (class "Default")
      (node (ref "D3") (pin "2") (pinfunction "2_2") (pintype "passive"))
      (node (ref "R2") (pin "2") (pinfunction "2_2") (pintype "passive"))
    )
    (net (code "49") (name "Net-(D5-Pad2)") (class "Default")
      (node (ref "D5") (pin "2") (pinfunction "2_2") (pintype "passive"))
      (node (ref "R4") (pin "2") (pinfunction "2_2") (pintype "passive"))
    )
    (net (code "50") (name "Net-(P7-D+)") (class "Default")
      (node (ref "P7") (pin "3") (pinfunction "D+_3") (pintype "passive"))
      (node (ref "R25") (pin "2") (pinfunction "2_2") (pintype "passive"))
    )
    (net (code "51") (name "Net-(P7-D-)") (class "Default")
      (node (ref "P7") (pin "2") (pinfunction "D-_2") (pintype "passive"))
      (node (ref "R24") (pin "2") (pinfunction "2_2") (pintype "passive"))
    )
    (net (code "52") (name "Net-(P7-ID)") (class "Default")
      (node (ref "P7") (pin "4") (pinfunction "ID_4") (pintype "passive"))
      (node (ref "R26") (pin "2") (pinfunction "2_2") (pintype "passive"))
    )
    (net (code "53") (name "Net-(Q1-B)") (class "Default")
      (node (ref "Q1") (pin "1") (pinfunction "B_1") (pintype "passive"))
      (node (ref "R3") (pin "1") (pinfunction "1_1") (pintype "passive"))
    )
    (net (code "54") (name "Net-(Q2-B)") (class "Default")
      (node (ref "Q2") (pin "1") (pinfunction "B_1") (pintype "passive"))
      (node (ref "Q3") (pin "3") (pinfunction "C_3") (pintype "passive"))
      (node (ref "R12") (pin "2") (pinfunction "2_2") (pintype "passive"))
      (node (ref "R18") (pin "1") (pinfunction "1_1") (pintype "passive"))
    )
    (net (code "55") (name "Net-(Q2-E)") (class "Default")
      (node (ref "Q2") (pin "2") (pinfunction "E_2") (pintype "passive"))
      (node (ref "R21") (pin "2") (pinfunction "2_2") (pintype "passive"))
    )
    (net (code "56") (name "Net-(Q3-B)") (class "Default")
      (node (ref "Q3") (pin "1") (pinfunction "B_1") (pintype "passive"))
      (node (ref "R16") (pin "2") (pinfunction "2_2") (pintype "passive"))
      (node (ref "R19") (pin "2") (pinfunction "2_2") (pintype "passive"))
    )
    (net (code "57") (name "Net-(U1-VOUT)") (class "Default")
      (node (ref "C3") (pin "1") (pinfunction "1_1") (pintype "passive"))
      (node (ref "C5") (pin "2") (pinfunction "2_2") (pintype "passive"))
      (node (ref "R1") (pin "2") (pinfunction "2_2") (pintype "passive"))
      (node (ref "U1") (pin "1") (pinfunction "VOUT_1") (pintype "power_in"))
    )
    (net (code "58") (name "Net-(U2-IN)") (class "Default")
      (node (ref "C7") (pin "2") (pinfunction "2_2") (pintype "passive"))
      (node (ref "C8") (pin "1") (pinfunction "1_1") (pintype "passive"))
      (node (ref "L1") (pin "2") (pinfunction "2_2") (pintype "passive"))
      (node (ref "U2") (pin "3") (pinfunction "IN_3") (pintype "power_in"))
    )
    (net (code "59") (name "Net-(U3B-VBAT)") (class "Default")
      (node (ref "P6") (pin "2") (pinfunction "2_2") (pintype "passive"))
      (node (ref "R23") (pin "1") (pinfunction "1_1") (pintype "passive"))
      (node (ref "U3") (pin "1") (pinfunction "VBAT_1") (pintype "power_in"))
    )
    (net (code "60") (name "Net-(U3B-VDDA)") (class "Default")
      (node (ref "C34") (pin "2") (pinfunction "2_2") (pintype "passive"))
      (node (ref "C35") (pin "2") (pinfunction "2_2") (pintype "passive"))
      (node (ref "R27") (pin "1") (pinfunction "1_1") (pintype "passive"))
      (node (ref "U3") (pin "9") (pinfunction "VDDA_9") (pintype "power_in"))
    )
    (net (code "61") (name "VSS") (class "Default")
      (node (ref "C1") (pin "2") (pinfunction "2_2") (pintype "passive"))
      (node (ref "C10") (pin "2") (pinfunction "2_2") (pintype "passive"))
      (node (ref "C11") (pin "2") (pinfunction "2_2") (pintype "passive"))
      (node (ref "C12") (pin "1") (pinfunction "1_1") (pintype "passive"))
      (node (ref "C13") (pin "2") (pinfunction "2_2") (pintype "passive"))
      (node (ref "C14") (pin "1") (pinfunction "1_1") (pintype "passive"))
      (node (ref "C15") (pin "2") (pinfunction "2_2") (pintype "passive"))
      (node (ref "C16") (pin "2") (pinfunction "2_2") (pintype "passive"))
      (node (ref "C17") (pin "2") (pinfunction "2_2") (pintype "passive"))
      (node (ref "C18") (pin "2") (pinfunction "2_2") (pintype "passive"))
      (node (ref "C19") (pin "1") (pinfunction "1_1") (pintype "passive"))
      (node (ref "C2") (pin "2") (pinfunction "2_2") (pintype "passive"))
      (node (ref "C20") (pin "2") (pinfunction "2_2") (pintype "passive"))
      (node (ref "C21") (pin "2") (pinfunction "2_2") (pintype "passive"))
      (node (ref "C22") (pin "2") (pinfunction "2_2") (pintype "passive"))
      (node (ref "C23") (pin "1") (pinfunction "1_1") (pintype "passive"))
      (node (ref "C24") (pin "2") (pinfunction "2_2") (pintype "passive"))
      (node (ref "C25") (pin "1") (pinfunction "1_1") (pintype "passive"))
      (node (ref "C26") (pin "2") (pinfunction "2_2") (pintype "passive"))
      (node (ref "C27") (pin "1") (pinfunction "1_1") (pintype "passive"))
      (node (ref "C28") (pin "1") (pinfunction "1_1") (pintype "passive"))
      (node (ref "C29") (pin "1") (pinfunction "1_1") (pintype "passive"))
      (node (ref "C3") (pin "2") (pinfunction "2_2") (pintype "passive"))
      (node (ref "C30") (pin "1") (pinfunction "1_1") (pintype "passive"))
      (node (ref "C31") (pin "1") (pinfunction "1_1") (pintype "passive"))
      (node (ref "C32") (pin "1") (pinfunction "1_1") (pintype "passive"))
      (node (ref "C33") (pin "1") (pinfunction "1_1") (pintype "passive"))
      (node (ref "C34") (pin "1") (pinfunction "1_1") (pintype "passive"))
      (node (ref "C35") (pin "1") (pinfunction "1_1") (pintype "passive"))
      (node (ref "C36") (pin "1") (pinfunction "1_1") (pintype "passive"))
      (node (ref "C4") (pin "1") (pinfunction "1_1") (pintype "passive"))
      (node (ref "C5") (pin "1") (pinfunction "1_1") (pintype "passive"))
      (node (ref "C6") (pin "1") (pinfunction "1_1") (pintype "passive"))
      (node (ref "C7") (pin "1") (pinfunction "1_1") (pintype "passive"))
      (node (ref "C8") (pin "2") (pinfunction "2_2") (pintype "passive"))
      (node (ref "C9") (pin "1") (pinfunction "1_1") (pintype "passive"))
      (node (ref "D4") (pin "1") (pinfunction "A_1") (pintype "passive"))
      (node (ref "D6") (pin "1") (pinfunction "A_1") (pintype "passive"))
      (node (ref "P1") (pin "1") (pinfunction "1_1") (pintype "passive"))
      (node (ref "P2") (pin "10") (pinfunction "10_10") (pintype "passive"))
      (node (ref "P3") (pin "10") (pinfunction "10_10") (pintype "passive"))
      (node (ref "P4") (pin "2") (pinfunction "2_2") (pintype "passive"))
      (node (ref "P5") (pin "6") (pinfunction "6_6") (pintype "passive"))
      (node (ref "P6") (pin "1") (pinfunction "1_1") (pintype "passive"))
      (node (ref "P7") (pin "5") (pinfunction "GND_5") (pintype "passive"))
      (node (ref "P7") (pin "6") (pinfunction "SHIELD_6") (pintype "passive"))
      (node (ref "P8") (pin "1") (pinfunction "1_1") (pintype "passive"))
      (node (ref "Q1") (pin "2") (pinfunction "E_2") (pintype "passive"))
      (node (ref "Q3") (pin "2") (pinfunction "E_2") (pintype "passive"))
      (node (ref "R18") (pin "2") (pinfunction "2_2") (pintype "passive"))
      (node (ref "R22") (pin "2") (pinfunction "2_2") (pintype "passive"))
      (node (ref "R26") (pin "1") (pinfunction "1_1") (pintype "passive"))
      (node (ref "U1") (pin "2") (pinfunction "GND_2") (pintype "power_in"))
      (node (ref "U2") (pin "1") (pinfunction "GND_1") (pintype "power_in"))
      (node (ref "U3") (pin "23") (pinfunction "VSS_1_23") (pintype "power_in"))
      (node (ref "U3") (pin "35") (pinfunction "VSS_2_35") (pintype "power_in"))
      (node (ref "U3") (pin "47") (pinfunction "VSS_3_47") (pintype "power_in"))
      (node (ref "U3") (pin "8") (pinfunction "VSSA_8") (pintype "power_in"))
      (node (ref "U4") (pin "1") (pinfunction "A0_1") (pintype "input"))
      (node (ref "U4") (pin "2") (pinfunction "A1_2") (pintype "input"))
      (node (ref "U4") (pin "3") (pinfunction "A2_3") (pintype "input"))
    )
    (net (code "62") (name "unconnected-(U4-VSS-Pad4)") (class "Default")
      (node (ref "U4") (pin "4") (pinfunction "VSS_4") (pintype "power_in"))
    )
  )
)
